# XORXNOR1.net
KiCad netlist of a schematic drawn in Altium Designer
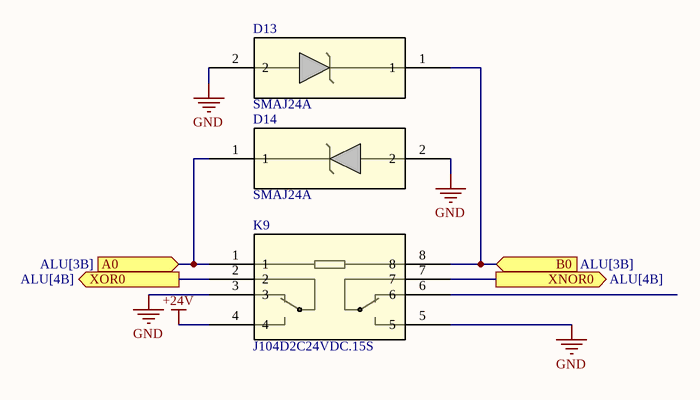
[diagram p0: XORXNOR1.SchDoc]

(export (version "E")
  (design (tool "Eeschema 10.0.6"))
  (components
    (comp (ref "D13")
      (value "SMAJ24A")
      (footprint "DI SMAJ24A")
      (description "SMAJ Series 400 W 24 V Uni-Directional Surface Mount TVS Diode - DO-214AC")
      (fields (field (name "MANUFACTURER") "Littelfuse"))
      (libsource (lib "Schlib1") (part "DI SMAJ24A"))
    )
    (comp (ref "D14")
      (value "SMAJ24A")
      (footprint "DI SMAJ24A")
      (description "SMAJ Series 400 W 24 V Uni-Directional Surface Mount TVS Diode - DO-214AC")
      (fields (field (name "MANUFACTURER") "Littelfuse"))
      (libsource (lib "") (part "DI SMAJ24A_1"))
    )
    (comp (ref "K9")
      (value "J104D2C24VDC.15S")
      (footprint "Relay J104D2C24VDC.15S")
      (description "Relay Ul Gen Purp DPDT 2C 24VDC")
      (fields (field (name "MANUFACTURER") "CIT Relay & Switch"))
      (libsource (lib "Schlib1") (part "Relay J104D2C24VDC.15S"))
    )
  )
  (nets
    (net (code "1") (name "+24V") (class "Default")
      (node (ref "K9") (pin "4") (pinfunction "4_4") (pintype "passive"))
    )
    (net (code "2") (name "/A0") (class "Default")
      (node (ref "D14") (pin "1") (pinfunction "1_1") (pintype "passive"))
      (node (ref "K9") (pin "1") (pinfunction "1_1") (pintype "passive"))
    )
    (net (code "3") (name "/B0") (class "Default")
      (node (ref "D13") (pin "1") (pinfunction "1_1") (pintype "passive"))
      (node (ref "K9") (pin "8") (pinfunction "8_8") (pintype "passive"))
    )
    (net (code "4") (name "/XNOR0") (class "Default")
      (node (ref "K9") (pin "7") (pinfunction "7_7") (pintype "passive"))
    )
    (net (code "5") (name "/XOR0") (class "Default")
      (node (ref "K9") (pin "2") (pinfunction "2_2") (pintype "passive"))
    )
    (net (code "6") (name "GND") (class "Default")
      (node (ref "D13") (pin "2") (pinfunction "2_2") (pintype "passive"))
      (node (ref "D14") (pin "2") (pinfunction "2_2") (pintype "passive"))
      (node (ref "K9") (pin "3") (pinfunction "3_3") (pintype "passive"))
      (node (ref "K9") (pin "5") (pinfunction "5_5") (pintype "passive"))
    )
    (net (code "7") (name "unconnected-(K9-Pad6)") (class "Default")
      (node (ref "K9") (pin "6") (pinfunction "6_6") (pintype "passive"))
    )
  )
)
